# boardV5.net
KiCad netlist of a schematic drawn in EAGLE
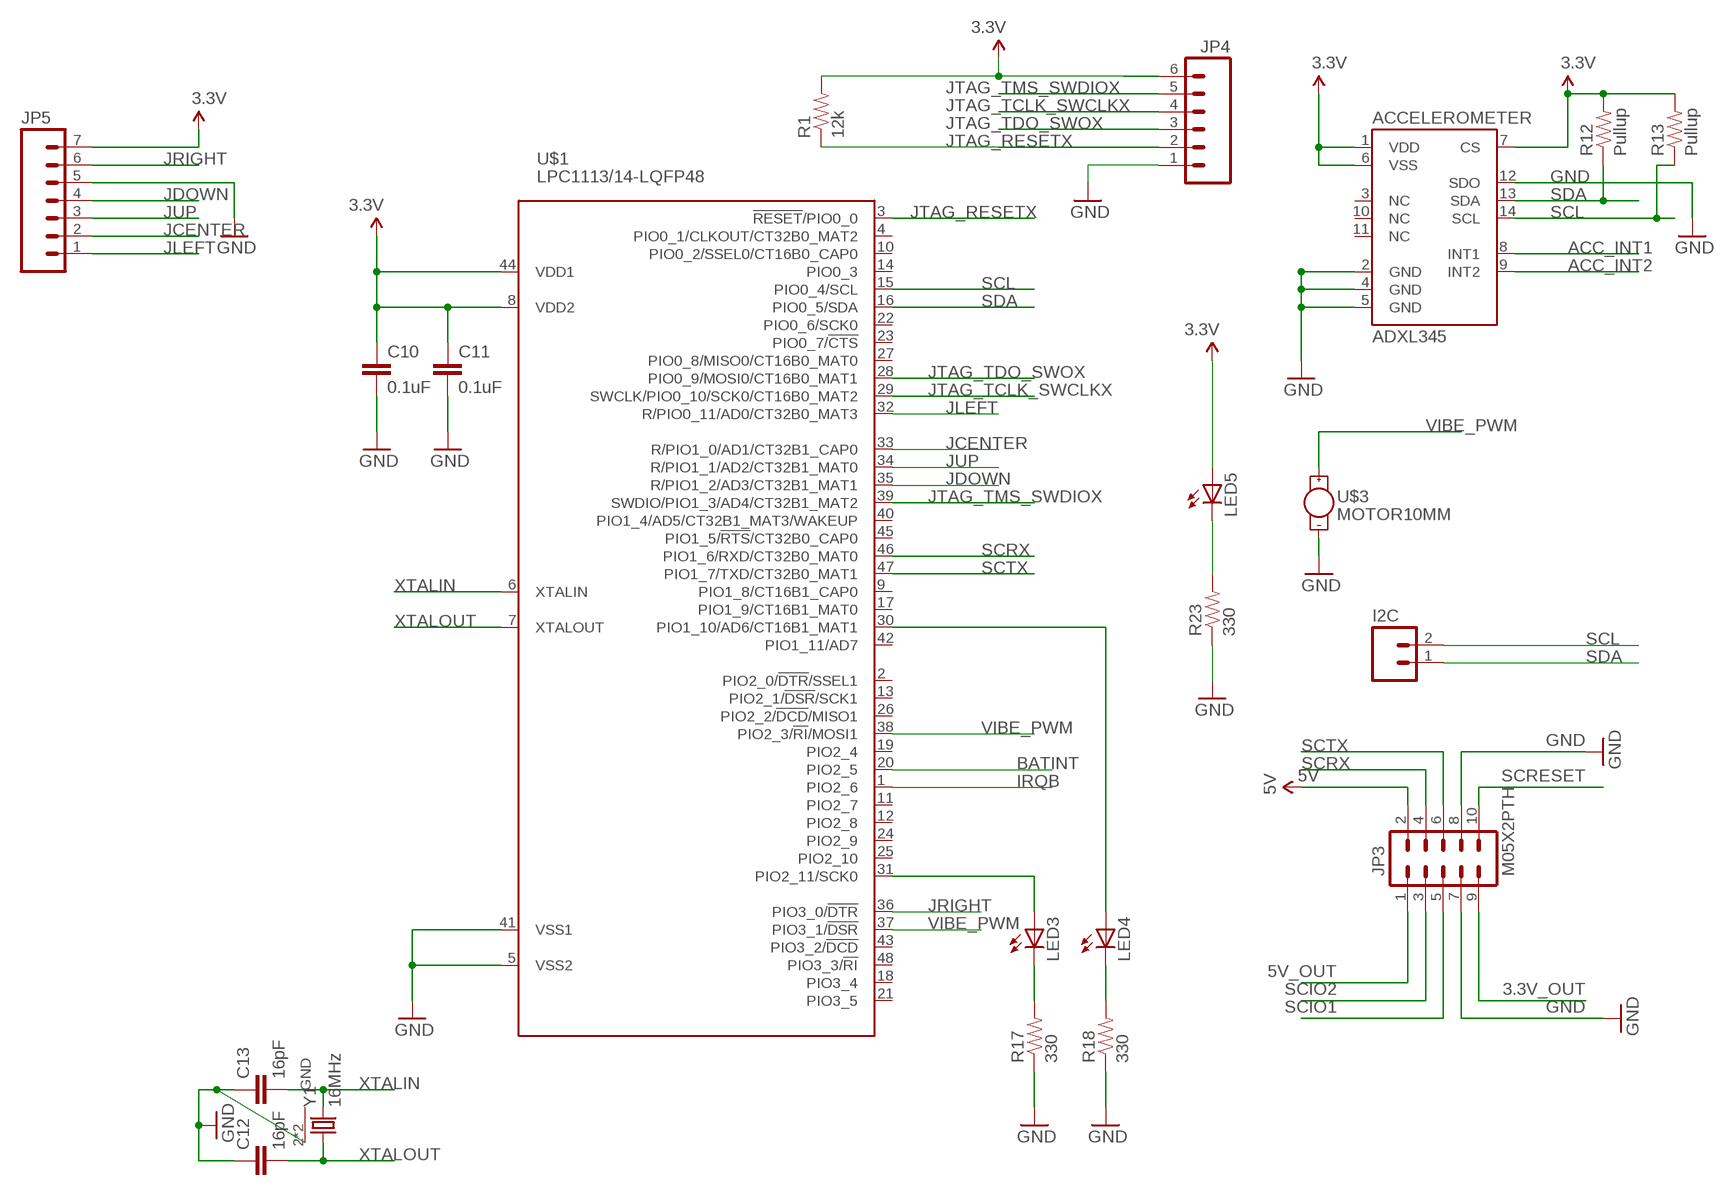
[diagram p0: schematic, sheet 1]
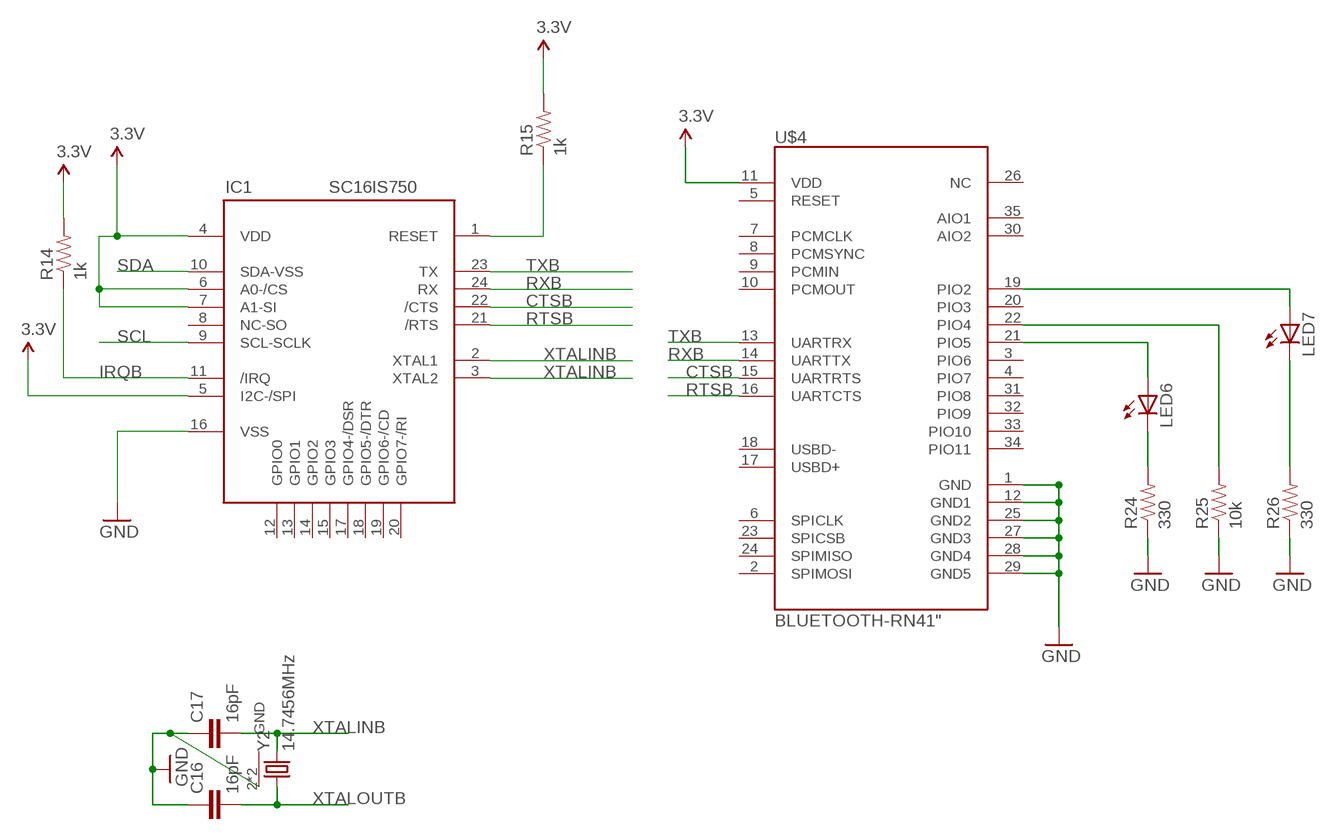
[diagram p1: schematic, sheet 3]
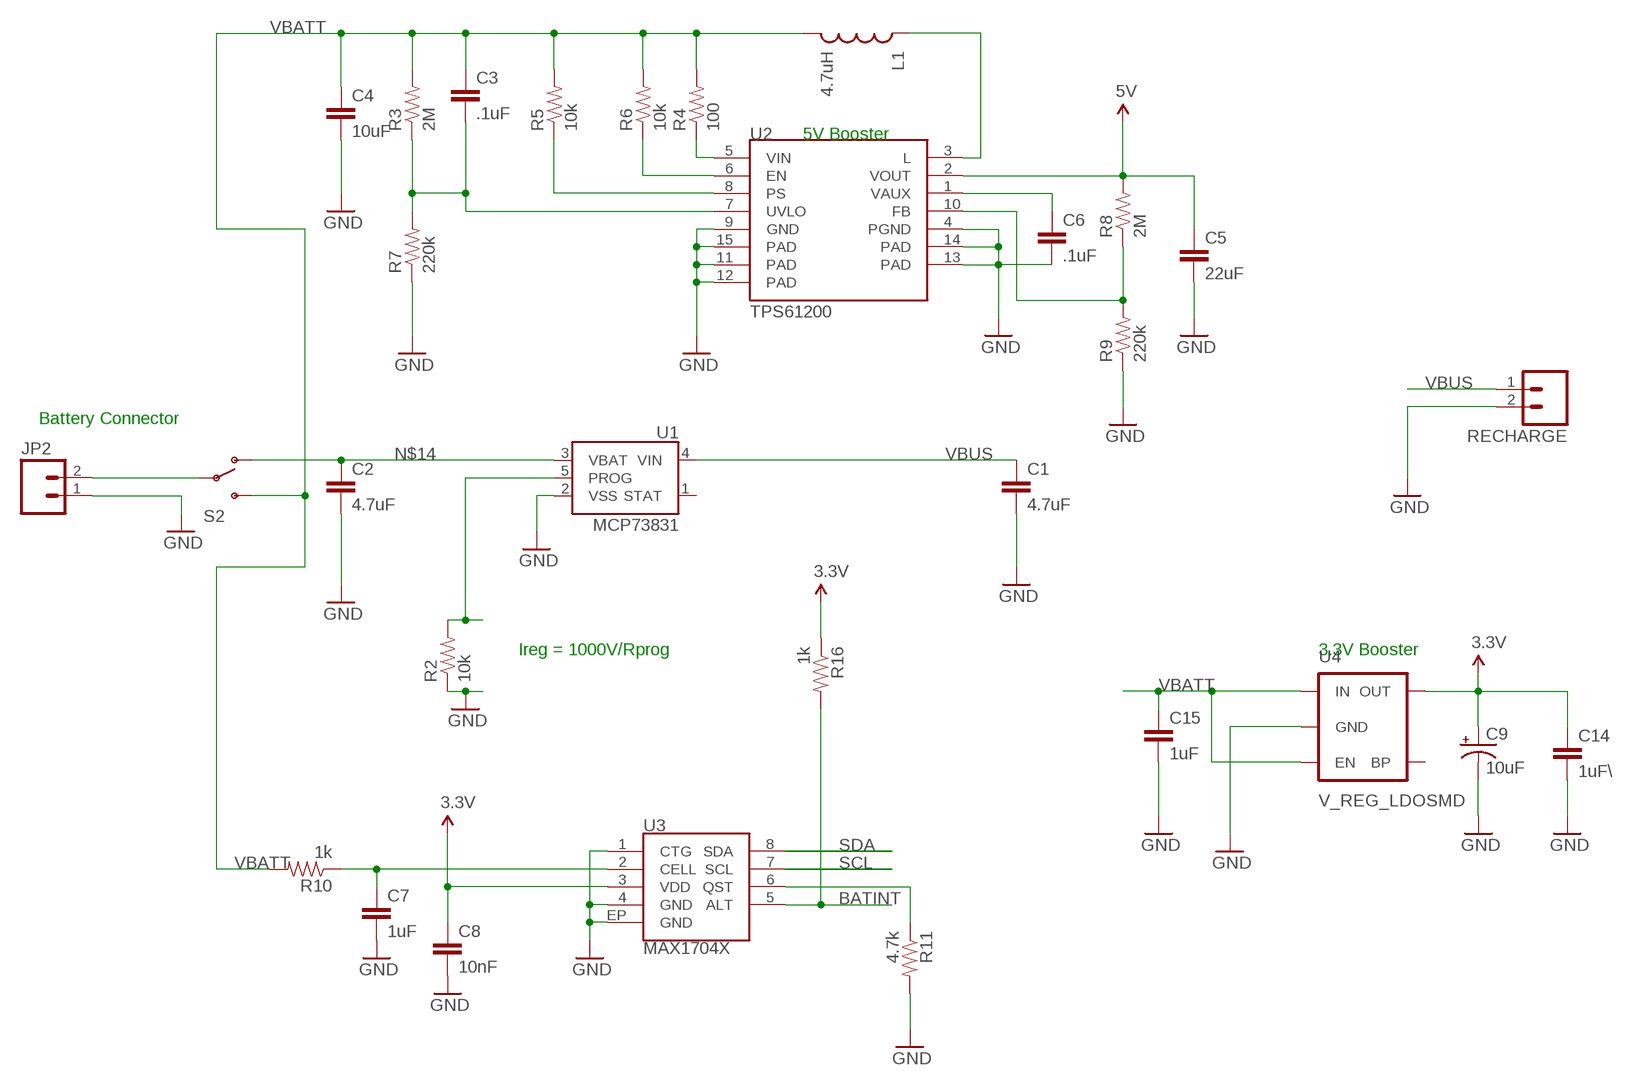
[diagram p2: schematic, sheet 4]

(export (version "E")
  (design (tool "Eeschema 10.0.6"))
  (components
    (comp (ref "ACCELEROMETER")
      (value "ADXL345")
      (footprint "eagle-import:LGA14")
      (libsource (lib "eagle-import") (part "ADXL345"))
    )
    (comp (ref "C10")
      (value "0.1uF")
      (footprint "eagle-import:0603-CAP")
      (libsource (lib "eagle-import") (part "CAP0603-CAP"))
    )
    (comp (ref "C11")
      (value "0.1uF")
      (footprint "eagle-import:0603-CAP")
      (libsource (lib "eagle-import") (part "CAP0603-CAP"))
    )
    (comp (ref "C12")
      (value "16pF")
      (footprint "eagle-import:0603-CAP")
      (libsource (lib "eagle-import") (part "CAP0603-CAP"))
    )
    (comp (ref "C13")
      (value "16pF")
      (footprint "eagle-import:0603-CAP")
      (libsource (lib "eagle-import") (part "CAP0603-CAP"))
    )
    (comp (ref "I2C")
      (value "M02POLAR")
      (footprint "eagle-import:MOLEX-1X2")
      (libsource (lib "eagle-import") (part "M02POLAR"))
    )
    (comp (ref "JP3")
      (value "M05X2PTH")
      (footprint "eagle-import:AVR_ICSP")
      (libsource (lib "eagle-import") (part "M05X2PTH"))
    )
    (comp (ref "JP4")
      (value "M06POLAR")
      (footprint "eagle-import:MOLEX-1X6")
      (libsource (lib "eagle-import") (part "M06POLAR"))
    )
    (comp (ref "JP5")
      (value "M07")
      (footprint "eagle-import:1X07")
      (libsource (lib "eagle-import") (part "M07"))
    )
    (comp (ref "LED3")
      (value "LED0603")
      (footprint "eagle-import:LED-0603")
      (libsource (lib "eagle-import") (part "LED0603"))
    )
    (comp (ref "LED4")
      (value "LED0603")
      (footprint "eagle-import:LED-0603")
      (libsource (lib "eagle-import") (part "LED0603"))
    )
    (comp (ref "LED5")
      (value "LED0603")
      (footprint "eagle-import:LED-0603")
      (libsource (lib "eagle-import") (part "LED0603"))
    )
    (comp (ref "R1")
      (value "12k")
      (footprint "eagle-import:0603-RES")
      (libsource (lib "eagle-import") (part "RESISTOR0603-RES"))
    )
    (comp (ref "R12")
      (value "Pullup")
      (footprint "eagle-import:0603-RES")
      (libsource (lib "eagle-import") (part "SparkFun-Resistors_RESISTOR0603-RES"))
    )
    (comp (ref "R13")
      (value "Pullup")
      (footprint "eagle-import:0603-RES")
      (libsource (lib "eagle-import") (part "SparkFun-Resistors_RESISTOR0603-RES"))
    )
    (comp (ref "R17")
      (value "330")
      (footprint "eagle-import:0603-RES")
      (libsource (lib "eagle-import") (part "RESISTOR0603-RES"))
    )
    (comp (ref "R18")
      (value "330")
      (footprint "eagle-import:0603-RES")
      (libsource (lib "eagle-import") (part "RESISTOR0603-RES"))
    )
    (comp (ref "R23")
      (value "330")
      (footprint "eagle-import:0603-RES")
      (libsource (lib "eagle-import") (part "RESISTOR0603-RES"))
    )
    (comp (ref "U$1")
      (value "LPC1113/14-LQFP48")
      (footprint "eagle-import:LQFP48")
      (libsource (lib "eagle-import") (part "LPC1113/14-LQFP48"))
    )
    (comp (ref "U$3")
      (value "MOTOR10MM")
      (footprint "eagle-import:VIBE-MOTOR-10MM")
      (libsource (lib "eagle-import") (part "MOTOR10MM"))
    )
    (comp (ref "Y1")
      (value "16MHz")
      (footprint "eagle-import:CRYSTAL-SMD-5X3")
      (libsource (lib "eagle-import") (part "CRYSTAL5X3"))
    )
    (comp (ref "C1")
      (value "4.7uF")
      (footprint "eagle-import:0603-CAP")
      (libsource (lib "eagle-import") (part "CAP0603-CAP"))
    )
    (comp (ref "C2")
      (value "4.7uF")
      (footprint "eagle-import:0603-CAP")
      (libsource (lib "eagle-import") (part "CAP0603-CAP"))
    )
    (comp (ref "C3")
      (value ".1uF")
      (footprint "eagle-import:0603-CAP")
      (libsource (lib "eagle-import") (part "CAP0603-CAP"))
    )
    (comp (ref "C4")
      (value "10uF")
      (footprint "eagle-import:0603-CAP")
      (libsource (lib "eagle-import") (part "CAP0603-CAP"))
    )
    (comp (ref "C5")
      (value "22uF")
      (footprint "eagle-import:0603-CAP")
      (libsource (lib "eagle-import") (part "CAP0603-CAP"))
    )
    (comp (ref "C6")
      (value ".1uF")
      (footprint "eagle-import:0603-CAP")
      (libsource (lib "eagle-import") (part "CAP0603-CAP"))
    )
    (comp (ref "C7")
      (value "1uF")
      (footprint "eagle-import:0603-CAP")
      (libsource (lib "eagle-import") (part "CAP0603-CAP"))
    )
    (comp (ref "C8")
      (value "10nF")
      (footprint "eagle-import:0603-CAP")
      (libsource (lib "eagle-import") (part "CAP0603-CAP"))
    )
    (comp (ref "C9")
      (value "10uF")
      (footprint "eagle-import:EIA3216")
      (libsource (lib "eagle-import") (part "10UF-TANT"))
    )
    (comp (ref "C14")
      (value "1uF\\")
      (footprint "eagle-import:0603-CAP")
      (libsource (lib "eagle-import") (part "CAP0603-CAP"))
    )
    (comp (ref "C15")
      (value "1uF")
      (footprint "eagle-import:0603-CAP")
      (libsource (lib "eagle-import") (part "CAP0603-CAP"))
    )
    (comp (ref "JP2")
      (value "M02PTH")
      (footprint "eagle-import:1X02")
      (libsource (lib "eagle-import") (part "M02PTH"))
    )
    (comp (ref "L1")
      (value "4.7uH")
      (footprint "eagle-import:CDRH2D09")
      (libsource (lib "eagle-import") (part "INDUCTOR."))
    )
    (comp (ref "R2")
      (value "10k")
      (footprint "eagle-import:0603-RES")
      (libsource (lib "eagle-import") (part "RESISTOR0603-RES"))
    )
    (comp (ref "R3")
      (value "2M")
      (footprint "eagle-import:0603-RES")
      (libsource (lib "eagle-import") (part "RESISTOR0603-RES"))
    )
    (comp (ref "R4")
      (value "100")
      (footprint "eagle-import:0603-RES")
      (libsource (lib "eagle-import") (part "RESISTOR0603-RES"))
    )
    (comp (ref "R5")
      (value "10k")
      (footprint "eagle-import:0603-RES")
      (libsource (lib "eagle-import") (part "RESISTOR0603-RES"))
    )
    (comp (ref "R6")
      (value "10k")
      (footprint "eagle-import:0603-RES")
      (libsource (lib "eagle-import") (part "RESISTOR0603-RES"))
    )
    (comp (ref "R7")
      (value "220k")
      (footprint "eagle-import:0603-RES")
      (libsource (lib "eagle-import") (part "RESISTOR0603-RES"))
    )
    (comp (ref "R8")
      (value "2M")
      (footprint "eagle-import:0603-RES")
      (libsource (lib "eagle-import") (part "SparkFun-Resistors_RESISTOR0603-RES"))
    )
    (comp (ref "R9")
      (value "220k")
      (footprint "eagle-import:0603-RES")
      (libsource (lib "eagle-import") (part "SparkFun-Resistors_RESISTOR0603-RES"))
    )
    (comp (ref "R10")
      (value "1k")
      (footprint "eagle-import:0603-RES")
      (libsource (lib "eagle-import") (part "RESISTOR0603-RES"))
    )
    (comp (ref "R11")
      (value "4.7k")
      (footprint "eagle-import:0603-RES")
      (libsource (lib "eagle-import") (part "RESISTOR0603-RES"))
    )
    (comp (ref "R16")
      (value "1k")
      (footprint "eagle-import:0603-RES")
      (libsource (lib "eagle-import") (part "RESISTOR0603-RES"))
    )
    (comp (ref "RECHARGE")
      (value "M02POLAR")
      (footprint "eagle-import:MOLEX-1X2")
      (libsource (lib "eagle-import") (part "M02POLAR"))
    )
    (comp (ref "S2")
      (value "SWITCH-SPDT-SMD-A")
      (footprint "eagle-import:SWITCH-SPST-SMD-A")
      (libsource (lib "eagle-import") (part "SWITCH-SPDT-SMD-A"))
    )
    (comp (ref "U1")
      (value "MCP73831")
      (footprint "eagle-import:SOT23-5")
      (libsource (lib "eagle-import") (part "MCP73831"))
    )
    (comp (ref "U2")
      (value "TPS61200")
      (footprint "eagle-import:QFN-10_PAD")
      (libsource (lib "eagle-import") (part "TPS61200"))
    )
    (comp (ref "U3")
      (value "MAX1704X")
      (footprint "eagle-import:TDFN-8")
      (libsource (lib "eagle-import") (part "MAX1704X"))
    )
    (comp (ref "U4")
      (value "V_REG_LDOSMD")
      (footprint "eagle-import:SOT23-5")
      (libsource (lib "eagle-import") (part "V_REG_LDOSMD"))
    )
    (comp (ref "C16")
      (value "16pF")
      (footprint "eagle-import:0603-CAP")
      (libsource (lib "eagle-import") (part "CAP0603-CAP"))
    )
    (comp (ref "C17")
      (value "16pF")
      (footprint "eagle-import:0603-CAP")
      (libsource (lib "eagle-import") (part "CAP0603-CAP"))
    )
    (comp (ref "IC1")
      (value "SC16IS750")
      (footprint "eagle-import:QFN-24")
      (libsource (lib "eagle-import") (part "SC16IS750"))
    )
    (comp (ref "LED6")
      (value "LED0603")
      (footprint "eagle-import:LED-0603")
      (libsource (lib "eagle-import") (part "LED0603"))
    )
    (comp (ref "LED7")
      (value "LED0603")
      (footprint "eagle-import:LED-0603")
      (libsource (lib "eagle-import") (part "LED0603"))
    )
    (comp (ref "R14")
      (value "1k")
      (footprint "eagle-import:0603-RES")
      (libsource (lib "eagle-import") (part "RESISTOR0603-RES"))
    )
    (comp (ref "R15")
      (value "1k")
      (footprint "eagle-import:0603-RES")
      (libsource (lib "eagle-import") (part "RESISTOR0603-RES"))
    )
    (comp (ref "R24")
      (value "330")
      (footprint "eagle-import:0603-RES")
      (libsource (lib "eagle-import") (part "RESISTOR0603-RES"))
    )
    (comp (ref "R25")
      (value "10k")
      (footprint "eagle-import:0603-RES")
      (libsource (lib "eagle-import") (part "RESISTOR0603-RES"))
    )
    (comp (ref "R26")
      (value "330")
      (footprint "eagle-import:0603-RES")
      (libsource (lib "eagle-import") (part "RESISTOR0603-RES"))
    )
    (comp (ref "U$4")
      (value "BLUETOOTH-RN41\"")
      (footprint "eagle-import:RN41")
      (libsource (lib "eagle-import") (part "BLUETOOTH-RN41{dblquote}"))
    )
    (comp (ref "Y2")
      (value "14.7456MHz")
      (footprint "eagle-import:CRYSTAL-SMD-5X3")
      (libsource (lib "eagle-import") (part "CRYSTAL5X3"))
    )
  )
  (nets
    (net (code "1") (name "3.3V") (class "Default")
      (node (ref "ACCELEROMETER") (pin "1") (pinfunction "VDD_1") (pintype "bidirectional"))
      (node (ref "ACCELEROMETER") (pin "6") (pinfunction "VSS_6") (pintype "bidirectional"))
      (node (ref "ACCELEROMETER") (pin "7") (pinfunction "CS_7") (pintype "bidirectional"))
      (node (ref "C10") (pin "1") (pinfunction "1_1") (pintype "passive"))
      (node (ref "C11") (pin "1") (pinfunction "1_1") (pintype "passive"))
      (node (ref "C14") (pin "1") (pinfunction "1_1") (pintype "passive"))
      (node (ref "C8") (pin "1") (pinfunction "1_1") (pintype "passive"))
      (node (ref "C9") (pin "A") (pinfunction "+_A") (pintype "passive"))
      (node (ref "IC1") (pin "4") (pinfunction "VDD_4") (pintype "bidirectional"))
      (node (ref "IC1") (pin "5") (pinfunction "I2C-/SPI_5") (pintype "bidirectional"))
      (node (ref "IC1") (pin "6") (pinfunction "A0-/CS_6") (pintype "bidirectional"))
      (node (ref "IC1") (pin "7") (pinfunction "A1-SI_7") (pintype "bidirectional"))
      (node (ref "JP4") (pin "6") (pinfunction "6_6") (pintype "passive"))
      (node (ref "JP5") (pin "7") (pinfunction "7_7") (pintype "passive"))
      (node (ref "LED5") (pin "A") (pinfunction "A_A") (pintype "passive"))
      (node (ref "R1") (pin "2") (pinfunction "2_2") (pintype "passive"))
      (node (ref "R12") (pin "2") (pinfunction "2_2") (pintype "passive"))
      (node (ref "R13") (pin "2") (pinfunction "2_2") (pintype "passive"))
      (node (ref "R14") (pin "2") (pinfunction "2_2") (pintype "passive"))
      (node (ref "R15") (pin "2") (pinfunction "2_2") (pintype "passive"))
      (node (ref "R16") (pin "1") (pinfunction "1_1") (pintype "passive"))
      (node (ref "U$1") (pin "44") (pinfunction "VDD1_44") (pintype "power_in"))
      (node (ref "U$1") (pin "8") (pinfunction "VDD2_8") (pintype "power_in"))
      (node (ref "U$4") (pin "11") (pinfunction "VDD_11") (pintype "bidirectional"))
      (node (ref "U3") (pin "3") (pinfunction "VDD_3") (pintype "bidirectional"))
      (node (ref "U4") (pin "5") (pinfunction "OUT_5") (pintype "passive"))
    )
    (net (code "2") (name "3.3V_OUT") (class "Default")
      (node (ref "JP3") (pin "9") (pinfunction "9_9") (pintype "passive"))
    )
    (net (code "3") (name "5V") (class "Default")
      (node (ref "C5") (pin "1") (pinfunction "1_1") (pintype "passive"))
      (node (ref "JP3") (pin "2") (pinfunction "2_2") (pintype "passive"))
      (node (ref "R8") (pin "2") (pinfunction "2_2") (pintype "passive"))
      (node (ref "U2") (pin "2") (pinfunction "VOUT_2") (pintype "passive"))
    )
    (net (code "4") (name "5V_OUT") (class "Default")
      (node (ref "JP3") (pin "1") (pinfunction "1_1") (pintype "passive"))
    )
    (net (code "5") (name "ACC_INT1") (class "Default")
      (node (ref "ACCELEROMETER") (pin "8") (pinfunction "INT1_8") (pintype "bidirectional"))
    )
    (net (code "6") (name "ACC_INT2") (class "Default")
      (node (ref "ACCELEROMETER") (pin "9") (pinfunction "INT2_9") (pintype "bidirectional"))
    )
    (net (code "7") (name "BATINT") (class "Default")
      (node (ref "R16") (pin "2") (pinfunction "2_2") (pintype "passive"))
      (node (ref "U$1") (pin "20") (pinfunction "PIO2_5_20") (pintype "bidirectional"))
      (node (ref "U3") (pin "5") (pinfunction "ALT_5") (pintype "bidirectional"))
    )
    (net (code "8") (name "CTSB") (class "Default")
      (node (ref "IC1") (pin "22") (pinfunction "/CTS_22") (pintype "bidirectional"))
      (node (ref "U$4") (pin "15") (pinfunction "UARTRTS_15") (pintype "bidirectional"))
    )
    (net (code "9") (name "GND") (class "Default")
      (node (ref "ACCELEROMETER") (pin "12") (pinfunction "SDO_12") (pintype "bidirectional"))
      (node (ref "ACCELEROMETER") (pin "2") (pinfunction "GND_2") (pintype "bidirectional"))
      (node (ref "ACCELEROMETER") (pin "4") (pinfunction "GND_4") (pintype "bidirectional"))
      (node (ref "ACCELEROMETER") (pin "5") (pinfunction "GND_5") (pintype "bidirectional"))
      (node (ref "C1") (pin "2") (pinfunction "2_2") (pintype "passive"))
      (node (ref "C10") (pin "2") (pinfunction "2_2") (pintype "passive"))
      (node (ref "C11") (pin "2") (pinfunction "2_2") (pintype "passive"))
      (node (ref "C12") (pin "1") (pinfunction "1_1") (pintype "passive"))
      (node (ref "C13") (pin "1") (pinfunction "1_1") (pintype "passive"))
      (node (ref "C14") (pin "2") (pinfunction "2_2") (pintype "passive"))
      (node (ref "C15") (pin "2") (pinfunction "2_2") (pintype "passive"))
      (node (ref "C16") (pin "1") (pinfunction "1_1") (pintype "passive"))
      (node (ref "C17") (pin "1") (pinfunction "1_1") (pintype "passive"))
      (node (ref "C2") (pin "2") (pinfunction "2_2") (pintype "passive"))
      (node (ref "C4") (pin "2") (pinfunction "2_2") (pintype "passive"))
      (node (ref "C5") (pin "2") (pinfunction "2_2") (pintype "passive"))
      (node (ref "C6") (pin "2") (pinfunction "2_2") (pintype "passive"))
      (node (ref "C7") (pin "2") (pinfunction "2_2") (pintype "passive"))
      (node (ref "C8") (pin "2") (pinfunction "2_2") (pintype "passive"))
      (node (ref "C9") (pin "C") (pinfunction "-_C") (pintype "passive"))
      (node (ref "IC1") (pin "16") (pinfunction "VSS_16") (pintype "bidirectional"))
      (node (ref "JP2") (pin "1") (pinfunction "1_1") (pintype "passive"))
      (node (ref "JP3") (pin "7") (pinfunction "7_7") (pintype "passive"))
      (node (ref "JP3") (pin "8") (pinfunction "8_8") (pintype "passive"))
      (node (ref "JP4") (pin "1") (pinfunction "1_1") (pintype "passive"))
      (node (ref "JP5") (pin "5") (pinfunction "5_5") (pintype "passive"))
      (node (ref "R11") (pin "2") (pinfunction "2_2") (pintype "passive"))
      (node (ref "R17") (pin "1") (pinfunction "1_1") (pintype "passive"))
      (node (ref "R18") (pin "1") (pinfunction "1_1") (pintype "passive"))
      (node (ref "R2") (pin "1") (pinfunction "1_1") (pintype "passive"))
      (node (ref "R23") (pin "1") (pinfunction "1_1") (pintype "passive"))
      (node (ref "R24") (pin "1") (pinfunction "1_1") (pintype "passive"))
      (node (ref "R25") (pin "1") (pinfunction "1_1") (pintype "passive"))
      (node (ref "R26") (pin "1") (pinfunction "1_1") (pintype "passive"))
      (node (ref "R7") (pin "1") (pinfunction "1_1") (pintype "passive"))
      (node (ref "R9") (pin "1") (pinfunction "1_1") (pintype "passive"))
      (node (ref "RECHARGE") (pin "2") (pinfunction "2_2") (pintype "passive"))
      (node (ref "U$1") (pin "41") (pinfunction "VSS1_41") (pintype "power_in"))
      (node (ref "U$1") (pin "5") (pinfunction "VSS2_5") (pintype "power_in"))
      (node (ref "U$3") (pin "-") (pinfunction "-_-") (pintype "bidirectional"))
      (node (ref "U$4") (pin "1") (pinfunction "GND_1") (pintype "bidirectional"))
      (node (ref "U$4") (pin "12") (pinfunction "GND1_12") (pintype "bidirectional"))
      (node (ref "U$4") (pin "25") (pinfunction "GND2_25") (pintype "bidirectional"))
      (node (ref "U$4") (pin "27") (pinfunction "GND3_27") (pintype "bidirectional"))
      (node (ref "U$4") (pin "28") (pinfunction "GND4_28") (pintype "bidirectional"))
      (node (ref "U$4") (pin "29") (pinfunction "GND5_29") (pintype "bidirectional"))
      (node (ref "U1") (pin "2") (pinfunction "VSS_2") (pintype "power_in"))
      (node (ref "U2") (pin "11") (pinfunction "PAD_11") (pintype "power_in"))
      (node (ref "U2") (pin "12") (pinfunction "PAD_12") (pintype "power_in"))
      (node (ref "U2") (pin "13") (pinfunction "PAD_13") (pintype "power_in"))
      (node (ref "U2") (pin "14") (pinfunction "PAD_14") (pintype "power_in"))
      (node (ref "U2") (pin "15") (pinfunction "PAD_15") (pintype "power_in"))
      (node (ref "U2") (pin "4") (pinfunction "PGND_4") (pintype "power_in"))
      (node (ref "U2") (pin "9") (pinfunction "GND_9") (pintype "power_in"))
      (node (ref "U3") (pin "1") (pinfunction "CTG_1") (pintype "bidirectional"))
      (node (ref "U3") (pin "4") (pinfunction "GND_4") (pintype "bidirectional"))
      (node (ref "U3") (pin "EP") (pinfunction "GND_EP") (pintype "bidirectional"))
      (node (ref "U4") (pin "2") (pinfunction "GND_2") (pintype "input"))
      (node (ref "Y1") (pin "2") (pinfunction "GND_2") (pintype "bidirectional"))
      (node (ref "Y1") (pin "4") (pinfunction "GND_4") (pintype "bidirectional"))
      (node (ref "Y2") (pin "2") (pinfunction "GND_2") (pintype "bidirectional"))
      (node (ref "Y2") (pin "4") (pinfunction "GND_4") (pintype "bidirectional"))
    )
    (net (code "10") (name "IRQB") (class "Default")
      (node (ref "IC1") (pin "11") (pinfunction "/IRQ_11") (pintype "bidirectional"))
      (node (ref "R14") (pin "1") (pinfunction "1_1") (pintype "passive"))
      (node (ref "U$1") (pin "1") (pinfunction "PIO2_6_1") (pintype "bidirectional"))
    )
    (net (code "11") (name "JCENTER") (class "Default")
      (node (ref "JP5") (pin "2") (pinfunction "2_2") (pintype "passive"))
      (node (ref "U$1") (pin "33") (pinfunction "R/PIO1_0/AD1/CT32B1_CAP0_33") (pintype "bidirectional"))
    )
    (net (code "12") (name "JDOWN") (class "Default")
      (node (ref "JP5") (pin "4") (pinfunction "4_4") (pintype "passive"))
      (node (ref "U$1") (pin "35") (pinfunction "R/PIO1_2/AD3/CT32B1_MAT1_35") (pintype "bidirectional"))
    )
    (net (code "13") (name "JLEFT") (class "Default")
      (node (ref "JP5") (pin "1") (pinfunction "1_1") (pintype "passive"))
      (node (ref "U$1") (pin "32") (pinfunction "R/PIO0_11/AD0/CT32B0_MAT3_32") (pintype "bidirectional"))
    )
    (net (code "14") (name "JRIGHT") (class "Default")
      (node (ref "JP5") (pin "6") (pinfunction "6_6") (pintype "passive"))
      (node (ref "U$1") (pin "36") (pinfunction "PIO3_0/~{DTR}_36") (pintype "bidirectional"))
    )
    (net (code "15") (name "JTAG_RESETX") (class "Default")
      (node (ref "JP4") (pin "2") (pinfunction "2_2") (pintype "passive"))
      (node (ref "R1") (pin "1") (pinfunction "1_1") (pintype "passive"))
      (node (ref "U$1") (pin "3") (pinfunction "~{RESET}/PIO0_0_3") (pintype "bidirectional"))
    )
    (net (code "16") (name "JTAG_TCLK_SWCLKX") (class "Default")
      (node (ref "JP4") (pin "4") (pinfunction "4_4") (pintype "passive"))
      (node (ref "U$1") (pin "29") (pinfunction "SWCLK/PIO0_10/SCK0/CT16B0_MAT2_29") (pintype "bidirectional"))
    )
    (net (code "17") (name "JTAG_TDO_SWOX") (class "Default")
      (node (ref "JP4") (pin "3") (pinfunction "3_3") (pintype "passive"))
      (node (ref "U$1") (pin "28") (pinfunction "PIO0_9/MOSI0/CT16B0_MAT1_28") (pintype "bidirectional"))
    )
    (net (code "18") (name "JTAG_TMS_SWDIOX") (class "Default")
      (node (ref "JP4") (pin "5") (pinfunction "5_5") (pintype "passive"))
      (node (ref "U$1") (pin "39") (pinfunction "SWDIO/PIO1_3/AD4/CT32B1_MAT2_39") (pintype "bidirectional"))
    )
    (net (code "19") (name "JUP") (class "Default")
      (node (ref "JP5") (pin "3") (pinfunction "3_3") (pintype "passive"))
      (node (ref "U$1") (pin "34") (pinfunction "R/PIO1_1/AD2/CT32B1_MAT0_34") (pintype "bidirectional"))
    )
    (net (code "20") (name "N$14") (class "Default")
      (node (ref "C2") (pin "1") (pinfunction "1_1") (pintype "passive"))
      (node (ref "S2") (pin "1") (pinfunction "O_1") (pintype "passive"))
      (node (ref "U1") (pin "3") (pinfunction "VBAT_3") (pintype "power_in"))
    )
    (net (code "21") (name "Net-(IC1-RESET)") (class "Default")
      (node (ref "IC1") (pin "1") (pinfunction "RESET_1") (pintype "bidirectional"))
      (node (ref "R15") (pin "1") (pinfunction "1_1") (pintype "passive"))
    )
    (net (code "22") (name "Net-(L1-1)") (class "Default")
      (node (ref "L1") (pin "P$1") (pinfunction "1_P$1") (pintype "passive"))
      (node (ref "U2") (pin "3") (pinfunction "L_3") (pintype "passive"))
    )
    (net (code "23") (name "Net-(LED3-PadC)") (class "Default")
      (node (ref "LED3") (pin "C") (pinfunction "C_C") (pintype "passive"))
      (node (ref "R17") (pin "2") (pinfunction "2_2") (pintype "passive"))
    )
    (net (code "24") (name "Net-(LED4-PadC)") (class "Default")
      (node (ref "LED4") (pin "C") (pinfunction "C_C") (pintype "passive"))
      (node (ref "R18") (pin "2") (pinfunction "2_2") (pintype "passive"))
    )
    (net (code "25") (name "Net-(LED5-PadC)") (class "Default")
      (node (ref "LED5") (pin "C") (pinfunction "C_C") (pintype "passive"))
      (node (ref "R23") (pin "2") (pinfunction "2_2") (pintype "passive"))
    )
    (net (code "26") (name "Net-(LED6-PadC)") (class "Default")
      (node (ref "LED6") (pin "C") (pinfunction "C_C") (pintype "passive"))
      (node (ref "R24") (pin "2") (pinfunction "2_2") (pintype "passive"))
    )
    (net (code "27") (name "Net-(LED7-PadC)") (class "Default")
      (node (ref "LED7") (pin "C") (pinfunction "C_C") (pintype "passive"))
      (node (ref "R26") (pin "2") (pinfunction "2_2") (pintype "passive"))
    )
    (net (code "28") (name "Net-(S2-P)") (class "Default")
      (node (ref "JP2") (pin "2") (pinfunction "2_2") (pintype "passive"))
      (node (ref "S2") (pin "2") (pinfunction "P_2") (pintype "passive"))
    )
    (net (code "29") (name "Net-(U$1-PIO1_10{slash}AD6{slash}CT16B1_MAT1)") (class "Default")
      (node (ref "LED4") (pin "A") (pinfunction "A_A") (pintype "passive"))
      (node (ref "U$1") (pin "30") (pinfunction "PIO1_10/AD6/CT16B1_MAT1_30") (pintype "bidirectional"))
    )
    (net (code "30") (name "Net-(U$1-PIO2_11{slash}SCK0)") (class "Default")
      (node (ref "LED3") (pin "A") (pinfunction "A_A") (pintype "passive"))
      (node (ref "U$1") (pin "31") (pinfunction "PIO2_11/SCK0_31") (pintype "bidirectional"))
    )
    (net (code "31") (name "Net-(U$4-PIO2)") (class "Default")
      (node (ref "LED7") (pin "A") (pinfunction "A_A") (pintype "passive"))
      (node (ref "U$4") (pin "19") (pinfunction "PIO2_19") (pintype "bidirectional"))
    )
    (net (code "32") (name "Net-(U$4-PIO4)") (class "Default")
      (node (ref "R25") (pin "2") (pinfunction "2_2") (pintype "passive"))
      (node (ref "U$4") (pin "22") (pinfunction "PIO4_22") (pintype "bidirectional"))
    )
    (net (code "33") (name "Net-(U$4-PIO5)") (class "Default")
      (node (ref "LED6") (pin "A") (pinfunction "A_A") (pintype "passive"))
      (node (ref "U$4") (pin "21") (pinfunction "PIO5_21") (pintype "bidirectional"))
    )
    (net (code "34") (name "Net-(U1-PROG)") (class "Default")
      (node (ref "R2") (pin "2") (pinfunction "2_2") (pintype "passive"))
      (node (ref "U1") (pin "5") (pinfunction "PROG_5") (pintype "input"))
    )
    (net (code "35") (name "Net-(U2-EN)") (class "Default")
      (node (ref "R6") (pin "1") (pinfunction "1_1") (pintype "passive"))
      (node (ref "U2") (pin "6") (pinfunction "EN_6") (pintype "input"))
    )
    (net (code "36") (name "Net-(U2-FB)") (class "Default")
      (node (ref "R8") (pin "1") (pinfunction "1_1") (pintype "passive"))
      (node (ref "R9") (pin "2") (pinfunction "2_2") (pintype "passive"))
      (node (ref "U2") (pin "10") (pinfunction "FB_10") (pintype "passive"))
    )
    (net (code "37") (name "Net-(U2-PS)") (class "Default")
      (node (ref "R5") (pin "1") (pinfunction "1_1") (pintype "passive"))
      (node (ref "U2") (pin "8") (pinfunction "PS_8") (pintype "input"))
    )
    (net (code "38") (name "Net-(U2-UVLO)") (class "Default")
      (node (ref "C3") (pin "2") (pinfunction "2_2") (pintype "passive"))
      (node (ref "R3") (pin "1") (pinfunction "1_1") (pintype "passive"))
      (node (ref "R7") (pin "2") (pinfunction "2_2") (pintype "passive"))
      (node (ref "U2") (pin "7") (pinfunction "UVLO_7") (pintype "passive"))
    )
    (net (code "39") (name "Net-(U2-VAUX)") (class "Default")
      (node (ref "C6") (pin "1") (pinfunction "1_1") (pintype "passive"))
      (node (ref "U2") (pin "1") (pinfunction "VAUX_1") (pintype "passive"))
    )
    (net (code "40") (name "Net-(U2-VIN)") (class "Default")
      (node (ref "R4") (pin "1") (pinfunction "1_1") (pintype "passive"))
      (node (ref "U2") (pin "5") (pinfunction "VIN_5") (pintype "power_in"))
    )
    (net (code "41") (name "Net-(U3-CELL)") (class "Default")
      (node (ref "C7") (pin "1") (pinfunction "1_1") (pintype "passive"))
      (node (ref "R10") (pin "1") (pinfunction "1_1") (pintype "passive"))
      (node (ref "U3") (pin "2") (pinfunction "CELL_2") (pintype "bidirectional"))
    )
    (net (code "42") (name "Net-(U3-QST)") (class "Default")
      (node (ref "R11") (pin "1") (pinfunction "1_1") (pintype "passive"))
      (node (ref "U3") (pin "6") (pinfunction "QST_6") (pintype "bidirectional"))
    )
    (net (code "43") (name "RTSB") (class "Default")
      (node (ref "IC1") (pin "21") (pinfunction "/RTS_21") (pintype "bidirectional"))
      (node (ref "U$4") (pin "16") (pinfunction "UARTCTS_16") (pintype "bidirectional"))
    )
    (net (code "44") (name "RXB") (class "Default")
      (node (ref "IC1") (pin "24") (pinfunction "RX_24") (pintype "bidirectional"))
      (node (ref "U$4") (pin "14") (pinfunction "UARTTX_14") (pintype "bidirectional"))
    )
    (net (code "45") (name "SCIO1") (class "Default")
      (node (ref "JP3") (pin "5") (pinfunction "5_5") (pintype "passive"))
    )
    (net (code "46") (name "SCIO2") (class "Default")
      (node (ref "JP3") (pin "3") (pinfunction "3_3") (pintype "passive"))
    )
    (net (code "47") (name "SCL") (class "Default")
      (node (ref "ACCELEROMETER") (pin "14") (pinfunction "SCL_14") (pintype "bidirectional"))
      (node (ref "I2C") (pin "2") (pinfunction "2_2") (pintype "passive"))
      (node (ref "IC1") (pin "9") (pinfunction "SCL-SCLK_9") (pintype "bidirectional"))
      (node (ref "R13") (pin "1") (pinfunction "1_1") (pintype "passive"))
      (node (ref "U$1") (pin "15") (pinfunction "PIO0_4/SCL_15") (pintype "bidirectional"))
      (node (ref "U3") (pin "7") (pinfunction "SCL_7") (pintype "bidirectional"))
    )
    (net (code "48") (name "SCRESET") (class "Default")
      (node (ref "JP3") (pin "10") (pinfunction "10_10") (pintype "passive"))
    )
    (net (code "49") (name "SCRX") (class "Default")
      (node (ref "JP3") (pin "4") (pinfunction "4_4") (pintype "passive"))
      (node (ref "U$1") (pin "46") (pinfunction "PIO1_6/RXD/CT32B0_MAT0_46") (pintype "bidirectional"))
    )
    (net (code "50") (name "SCTX") (class "Default")
      (node (ref "JP3") (pin "6") (pinfunction "6_6") (pintype "passive"))
      (node (ref "U$1") (pin "47") (pinfunction "PIO1_7/TXD/CT32B0_MAT1_47") (pintype "bidirectional"))
    )
    (net (code "51") (name "SDA") (class "Default")
      (node (ref "ACCELEROMETER") (pin "13") (pinfunction "SDA_13") (pintype "bidirectional"))
      (node (ref "I2C") (pin "1") (pinfunction "1_1") (pintype "passive"))
      (node (ref "IC1") (pin "10") (pinfunction "SDA-VSS_10") (pintype "bidirectional"))
      (node (ref "R12") (pin "1") (pinfunction "1_1") (pintype "passive"))
      (node (ref "U$1") (pin "16") (pinfunction "PIO0_5/SDA_16") (pintype "bidirectional"))
      (node (ref "U3") (pin "8") (pinfunction "SDA_8") (pintype "bidirectional"))
    )
    (net (code "52") (name "TXB") (class "Default")
      (node (ref "IC1") (pin "23") (pinfunction "TX_23") (pintype "bidirectional"))
      (node (ref "U$4") (pin "13") (pinfunction "UARTRX_13") (pintype "bidirectional"))
    )
    (net (code "53") (name "VBATT") (class "Default")
      (node (ref "C15") (pin "1") (pinfunction "1_1") (pintype "passive"))
      (node (ref "C3") (pin "1") (pinfunction "1_1") (pintype "passive"))
      (node (ref "C4") (pin "1") (pinfunction "1_1") (pintype "passive"))
      (node (ref "L1") (pin "P$2") (pinfunction "2_P$2") (pintype "passive"))
      (node (ref "R10") (pin "2") (pinfunction "2_2") (pintype "passive"))
      (node (ref "R3") (pin "2") (pinfunction "2_2") (pintype "passive"))
      (node (ref "R4") (pin "2") (pinfunction "2_2") (pintype "passive"))
      (node (ref "R5") (pin "2") (pinfunction "2_2") (pintype "passive"))
      (node (ref "R6") (pin "2") (pinfunction "2_2") (pintype "passive"))
      (node (ref "S2") (pin "3") (pinfunction "S_3") (pintype "passive"))
      (node (ref "U4") (pin "1") (pinfunction "IN_1") (pintype "input"))
      (node (ref "U4") (pin "3") (pinfunction "EN_3") (pintype "input"))
    )
    (net (code "54") (name "VBUS") (class "Default")
      (node (ref "C1") (pin "1") (pinfunction "1_1") (pintype "passive"))
      (node (ref "RECHARGE") (pin "1") (pinfunction "1_1") (pintype "passive"))
      (node (ref "U1") (pin "4") (pinfunction "VIN_4") (pintype "power_in"))
    )
    (net (code "55") (name "VIBE_PWM") (class "Default")
      (node (ref "U$1") (pin "37") (pinfunction "PIO3_1/~{DSR}_37") (pintype "bidirectional"))
      (node (ref "U$1") (pin "38") (pinfunction "PIO2_3/~{RI}/MOSI1_38") (pintype "bidirectional"))
      (node (ref "U$3") (pin "+") (pinfunction "+_+") (pintype "bidirectional"))
    )
    (net (code "56") (name "XTALIN") (class "Default")
      (node (ref "C13") (pin "2") (pinfunction "2_2") (pintype "passive"))
      (node (ref "U$1") (pin "6") (pinfunction "XTALIN_6") (pintype "passive"))
      (node (ref "Y1") (pin "3") (pinfunction "2_3") (pintype "passive"))
    )
    (net (code "57") (name "XTALINB") (class "Default")
      (node (ref "C17") (pin "2") (pinfunction "2_2") (pintype "passive"))
      (node (ref "IC1") (pin "2") (pinfunction "XTAL1_2") (pintype "bidirectional"))
      (node (ref "Y2") (pin "3") (pinfunction "2_3") (pintype "passive"))
    )
    (net (code "58") (name "XTALOUT") (class "Default")
      (node (ref "C12") (pin "2") (pinfunction "2_2") (pintype "passive"))
      (node (ref "U$1") (pin "7") (pinfunction "XTALOUT_7") (pintype "passive"))
      (node (ref "Y1") (pin "1") (pinfunction "1_1") (pintype "passive"))
    )
    (net (code "59") (name "XTALOUTB") (class "Default")
      (node (ref "C16") (pin "2") (pinfunction "2_2") (pintype "passive"))
      (node (ref "IC1") (pin "3") (pinfunction "XTAL2_3") (pintype "bidirectional"))
      (node (ref "Y2") (pin "1") (pinfunction "1_1") (pintype "passive"))
    )
    (net (code "60") (name "unconnected-(ACCELEROMETER-NC-Pad3)") (class "Default")
      (node (ref "ACCELEROMETER") (pin "3") (pinfunction "NC_3") (pintype "bidirectional"))
    )
    (net (code "61") (name "unconnected-(ACCELEROMETER-NC-Pad10)") (class "Default")
      (node (ref "ACCELEROMETER") (pin "10") (pinfunction "NC_10") (pintype "bidirectional"))
    )
    (net (code "62") (name "unconnected-(ACCELEROMETER-NC-Pad11)") (class "Default")
      (node (ref "ACCELEROMETER") (pin "11") (pinfunction "NC_11") (pintype "bidirectional"))
    )
    (net (code "63") (name "unconnected-(IC1-GPIO0-Pad12)") (class "Default")
      (node (ref "IC1") (pin "12") (pinfunction "GPIO0_12") (pintype "bidirectional"))
    )
    (net (code "64") (name "unconnected-(IC1-GPIO1-Pad13)") (class "Default")
      (node (ref "IC1") (pin "13") (pinfunction "GPIO1_13") (pintype "bidirectional"))
    )
    (net (code "65") (name "unconnected-(IC1-GPIO2-Pad14)") (class "Default")
      (node (ref "IC1") (pin "14") (pinfunction "GPIO2_14") (pintype "bidirectional"))
    )
    (net (code "66") (name "unconnected-(IC1-GPIO3-Pad15)") (class "Default")
      (node (ref "IC1") (pin "15") (pinfunction "GPIO3_15") (pintype "bidirectional"))
    )
    (net (code "67") (name "unconnected-(IC1-GPIO4-{slash}DSR-Pad17)") (class "Default")
      (node (ref "IC1") (pin "17") (pinfunction "GPIO4-/DSR_17") (pintype "bidirectional"))
    )
    (net (code "68") (name "unconnected-(IC1-GPIO5-{slash}DTR-Pad18)") (class "Default")
      (node (ref "IC1") (pin "18") (pinfunction "GPIO5-/DTR_18") (pintype "bidirectional"))
    )
    (net (code "69") (name "unconnected-(IC1-GPIO6-{slash}CD-Pad19)") (class "Default")
      (node (ref "IC1") (pin "19") (pinfunction "GPIO6-/CD_19") (pintype "bidirectional"))
    )
    (net (code "70") (name "unconnected-(IC1-GPIO7-{slash}RI-Pad20)") (class "Default")
      (node (ref "IC1") (pin "20") (pinfunction "GPIO7-/RI_20") (pintype "bidirectional"))
    )
    (net (code "71") (name "unconnected-(IC1-NC-SO-Pad8)") (class "Default")
      (node (ref "IC1") (pin "8") (pinfunction "NC-SO_8") (pintype "bidirectional"))
    )
    (net (code "72") (name "unconnected-(U$1-PIO0_1{slash}CLKOUT{slash}CT32B0_MAT2-Pad4)") (class "Default")
      (node (ref "U$1") (pin "4") (pinfunction "PIO0_1/CLKOUT/CT32B0_MAT2_4") (pintype "bidirectional"))
    )
    (net (code "73") (name "unconnected-(U$1-PIO0_2{slash}SSEL0{slash}CT16B0_CAP0-Pad10)") (class "Default")
      (node (ref "U$1") (pin "10") (pinfunction "PIO0_2/SSEL0/CT16B0_CAP0_10") (pintype "bidirectional"))
    )
    (net (code "74") (name "unconnected-(U$1-PIO0_3-Pad14)") (class "Default")
      (node (ref "U$1") (pin "14") (pinfunction "PIO0_3_14") (pintype "bidirectional"))
    )
    (net (code "75") (name "unconnected-(U$1-PIO0_6{slash}SCK0-Pad22)") (class "Default")
      (node (ref "U$1") (pin "22") (pinfunction "PIO0_6/SCK0_22") (pintype "bidirectional"))
    )
    (net (code "76") (name "unconnected-(U$1-PIO0_7{slash}~{CTS}-Pad23)") (class "Default")
      (node (ref "U$1") (pin "23") (pinfunction "PIO0_7/~{CTS}_23") (pintype "bidirectional"))
    )
    (net (code "77") (name "unconnected-(U$1-PIO0_8{slash}MISO0{slash}CT16B0_MAT0-Pad27)") (class "Default")
      (node (ref "U$1") (pin "27") (pinfunction "PIO0_8/MISO0/CT16B0_MAT0_27") (pintype "bidirectional"))
    )
    (net (code "78") (name "unconnected-(U$1-PIO1_4{slash}AD5{slash}CT32B1_MAT3{slash}WAKEUP-Pad40)") (class "Default")
      (node (ref "U$1") (pin "40") (pinfunction "PIO1_4/AD5/CT32B1_MAT3/WAKEUP_40") (pintype "bidirectional"))
    )
    (net (code "79") (name "unconnected-(U$1-PIO1_5{slash}~{RTS}{slash}CT32B0_CAP0-Pad45)") (class "Default")
      (node (ref "U$1") (pin "45") (pinfunction "PIO1_5/~{RTS}/CT32B0_CAP0_45") (pintype "bidirectional"))
    )
    (net (code "80") (name "unconnected-(U$1-PIO1_8{slash}CT16B1_CAP0-Pad9)") (class "Default")
      (node (ref "U$1") (pin "9") (pinfunction "PIO1_8/CT16B1_CAP0_9") (pintype "bidirectional"))
    )
    (net (code "81") (name "unconnected-(U$1-PIO1_9{slash}CT16B1_MAT0-Pad17)") (class "Default")
      (node (ref "U$1") (pin "17") (pinfunction "PIO1_9/CT16B1_MAT0_17") (pintype "bidirectional"))
    )
    (net (code "82") (name "unconnected-(U$1-PIO1_11{slash}AD7-Pad42)") (class "Default")
      (node (ref "U$1") (pin "42") (pinfunction "PIO1_11/AD7_42") (pintype "bidirectional"))
    )
    (net (code "83") (name "unconnected-(U$1-PIO2_0{slash}~{DTR}{slash}SSEL1-Pad2)") (class "Default")
      (node (ref "U$1") (pin "2") (pinfunction "PIO2_0/~{DTR}/SSEL1_2") (pintype "bidirectional"))
    )
    (net (code "84") (name "unconnected-(U$1-PIO2_1{slash}~{DSR}{slash}SCK1-Pad13)") (class "Default")
      (node (ref "U$1") (pin "13") (pinfunction "PIO2_1/~{DSR}/SCK1_13") (pintype "bidirectional"))
    )
    (net (code "85") (name "unconnected-(U$1-PIO2_2{slash}~{DCD}{slash}MISO1-Pad26)") (class "Default")
      (node (ref "U$1") (pin "26") (pinfunction "PIO2_2/~{DCD}/MISO1_26") (pintype "bidirectional"))
    )
    (net (code "86") (name "unconnected-(U$1-PIO2_4-Pad19)") (class "Default")
      (node (ref "U$1") (pin "19") (pinfunction "PIO2_4_19") (pintype "bidirectional"))
    )
    (net (code "87") (name "unconnected-(U$1-PIO2_7-Pad11)") (class "Default")
      (node (ref "U$1") (pin "11") (pinfunction "PIO2_7_11") (pintype "bidirectional"))
    )
    (net (code "88") (name "unconnected-(U$1-PIO2_8-Pad12)") (class "Default")
      (node (ref "U$1") (pin "12") (pinfunction "PIO2_8_12") (pintype "bidirectional"))
    )
    (net (code "89") (name "unconnected-(U$1-PIO2_9-Pad24)") (class "Default")
      (node (ref "U$1") (pin "24") (pinfunction "PIO2_9_24") (pintype "bidirectional"))
    )
    (net (code "90") (name "unconnected-(U$1-PIO2_10-Pad25)") (class "Default")
      (node (ref "U$1") (pin "25") (pinfunction "PIO2_10_25") (pintype "bidirectional"))
    )
    (net (code "91") (name "unconnected-(U$1-PIO3_2{slash}~{DCD}-Pad43)") (class "Default")
      (node (ref "U$1") (pin "43") (pinfunction "PIO3_2/~{DCD}_43") (pintype "bidirectional"))
    )
    (net (code "92") (name "unconnected-(U$1-PIO3_3{slash}~{RI}-Pad48)") (class "Default")
      (node (ref "U$1") (pin "48") (pinfunction "PIO3_3/~{RI}_48") (pintype "bidirectional"))
    )
    (net (code "93") (name "unconnected-(U$1-PIO3_4-Pad18)") (class "Default")
      (node (ref "U$1") (pin "18") (pinfunction "PIO3_4_18") (pintype "bidirectional"))
    )
    (net (code "94") (name "unconnected-(U$1-PIO3_5-Pad21)") (class "Default")
      (node (ref "U$1") (pin "21") (pinfunction "PIO3_5_21") (pintype "bidirectional"))
    )
    (net (code "95") (name "unconnected-(U$4-AIO1-Pad35)") (class "Default")
      (node (ref "U$4") (pin "35") (pinfunction "AIO1_35") (pintype "bidirectional"))
    )
    (net (code "96") (name "unconnected-(U$4-AIO2-Pad30)") (class "Default")
      (node (ref "U$4") (pin "30") (pinfunction "AIO2_30") (pintype "bidirectional"))
    )
    (net (code "97") (name "unconnected-(U$4-NC-Pad26)") (class "Default")
      (node (ref "U$4") (pin "26") (pinfunction "NC_26") (pintype "bidirectional"))
    )
    (net (code "98") (name "unconnected-(U$4-PCMCLK-Pad7)") (class "Default")
      (node (ref "U$4") (pin "7") (pinfunction "PCMCLK_7") (pintype "bidirectional"))
    )
    (net (code "99") (name "unconnected-(U$4-PCMIN-Pad9)") (class "Default")
      (node (ref "U$4") (pin "9") (pinfunction "PCMIN_9") (pintype "bidirectional"))
    )
    (net (code "100") (name "unconnected-(U$4-PCMOUT-Pad10)") (class "Default")
      (node (ref "U$4") (pin "10") (pinfunction "PCMOUT_10") (pintype "bidirectional"))
    )
    (net (code "101") (name "unconnected-(U$4-PCMSYNC-Pad8)") (class "Default")
      (node (ref "U$4") (pin "8") (pinfunction "PCMSYNC_8") (pintype "bidirectional"))
    )
    (net (code "102") (name "unconnected-(U$4-PIO3-Pad20)") (class "Default")
      (node (ref "U$4") (pin "20") (pinfunction "PIO3_20") (pintype "bidirectional"))
    )
    (net (code "103") (name "unconnected-(U$4-PIO6-Pad3)") (class "Default")
      (node (ref "U$4") (pin "3") (pinfunction "PIO6_3") (pintype "bidirectional"))
    )
    (net (code "104") (name "unconnected-(U$4-PIO7-Pad4)") (class "Default")
      (node (ref "U$4") (pin "4") (pinfunction "PIO7_4") (pintype "bidirectional"))
    )
    (net (code "105") (name "unconnected-(U$4-PIO8-Pad31)") (class "Default")
      (node (ref "U$4") (pin "31") (pinfunction "PIO8_31") (pintype "bidirectional"))
    )
    (net (code "106") (name "unconnected-(U$4-PIO9-Pad32)") (class "Default")
      (node (ref "U$4") (pin "32") (pinfunction "PIO9_32") (pintype "bidirectional"))
    )
    (net (code "107") (name "unconnected-(U$4-PIO10-Pad33)") (class "Default")
      (node (ref "U$4") (pin "33") (pinfunction "PIO10_33") (pintype "bidirectional"))
    )
    (net (code "108") (name "unconnected-(U$4-PIO11-Pad34)") (class "Default")
      (node (ref "U$4") (pin "34") (pinfunction "PIO11_34") (pintype "bidirectional"))
    )
    (net (code "109") (name "unconnected-(U$4-RESET-Pad5)") (class "Default")
      (node (ref "U$4") (pin "5") (pinfunction "RESET_5") (pintype "bidirectional"))
    )
    (net (code "110") (name "unconnected-(U$4-SPICLK-Pad6)") (class "Default")
      (node (ref "U$4") (pin "6") (pinfunction "SPICLK_6") (pintype "bidirectional"))
    )
    (net (code "111") (name "unconnected-(U$4-SPICSB-Pad23)") (class "Default")
      (node (ref "U$4") (pin "23") (pinfunction "SPICSB_23") (pintype "bidirectional"))
    )
    (net (code "112") (name "unconnected-(U$4-SPIMISO-Pad24)") (class "Default")
      (node (ref "U$4") (pin "24") (pinfunction "SPIMISO_24") (pintype "bidirectional"))
    )
    (net (code "113") (name "unconnected-(U$4-SPIMOSI-Pad2)") (class "Default")
      (node (ref "U$4") (pin "2") (pinfunction "SPIMOSI_2") (pintype "bidirectional"))
    )
    (net (code "114") (name "unconnected-(U$4-USBD+-Pad17)") (class "Default")
      (node (ref "U$4") (pin "17") (pinfunction "USBD+_17") (pintype "bidirectional"))
    )
    (net (code "115") (name "unconnected-(U$4-USBD--Pad18)") (class "Default")
      (node (ref "U$4") (pin "18") (pinfunction "USBD-_18") (pintype "bidirectional"))
    )
    (net (code "116") (name "unconnected-(U1-STAT-Pad1)") (class "Default")
      (node (ref "U1") (pin "1") (pinfunction "STAT_1") (pintype "output"))
    )
    (net (code "117") (name "unconnected-(U4-BP-Pad4)") (class "Default")
      (node (ref "U4") (pin "4") (pinfunction "BP_4") (pintype "input"))
    )
  )
)
